# WILD64_HDI.net
KiCad netlist of a schematic drawn in EAGLE
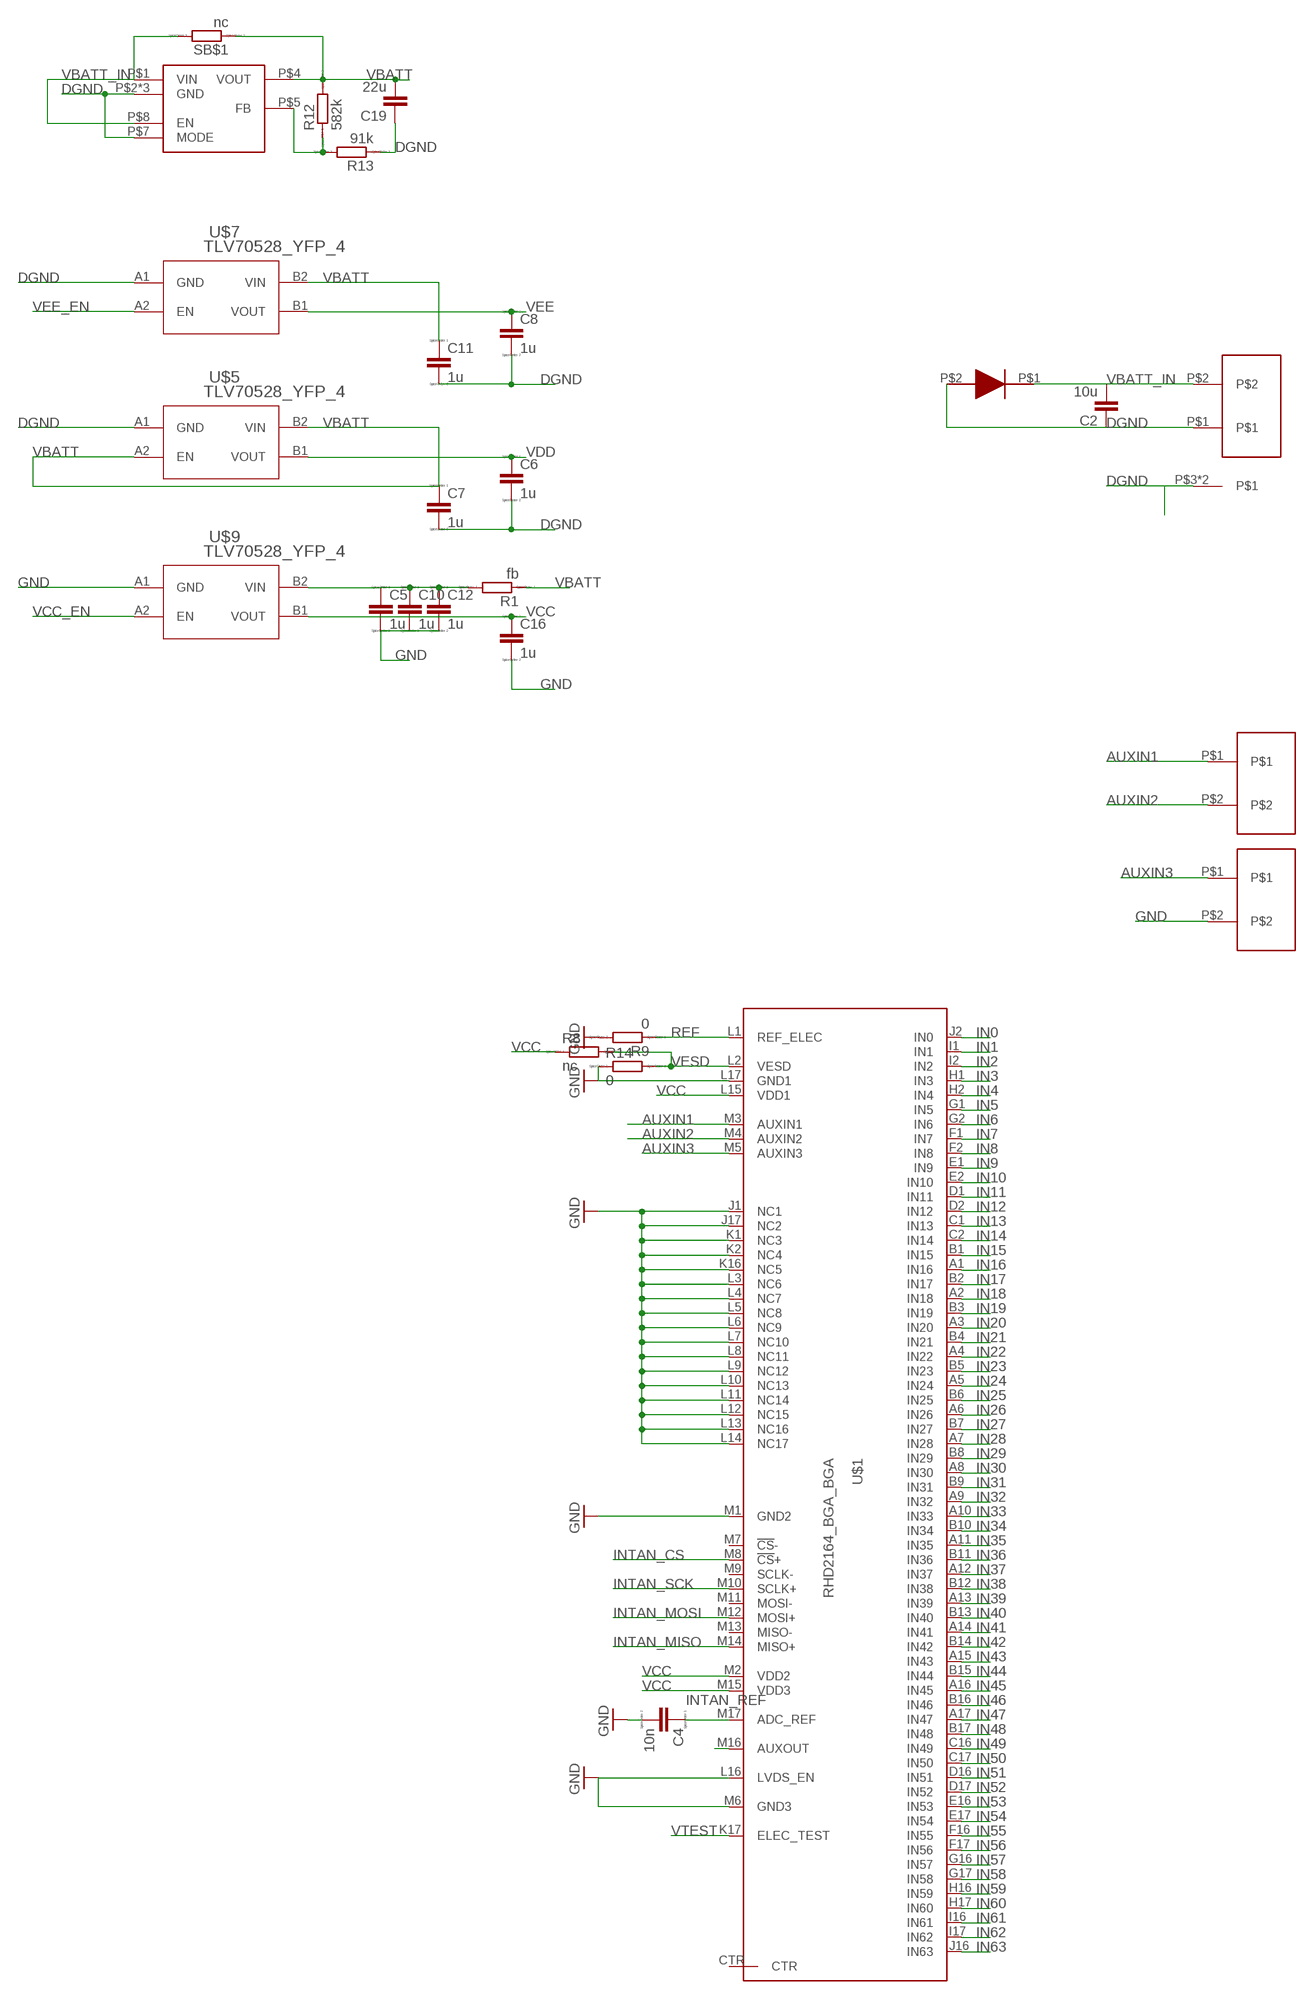
[diagram p0: schematic, sheet 1, part 1 of 2]
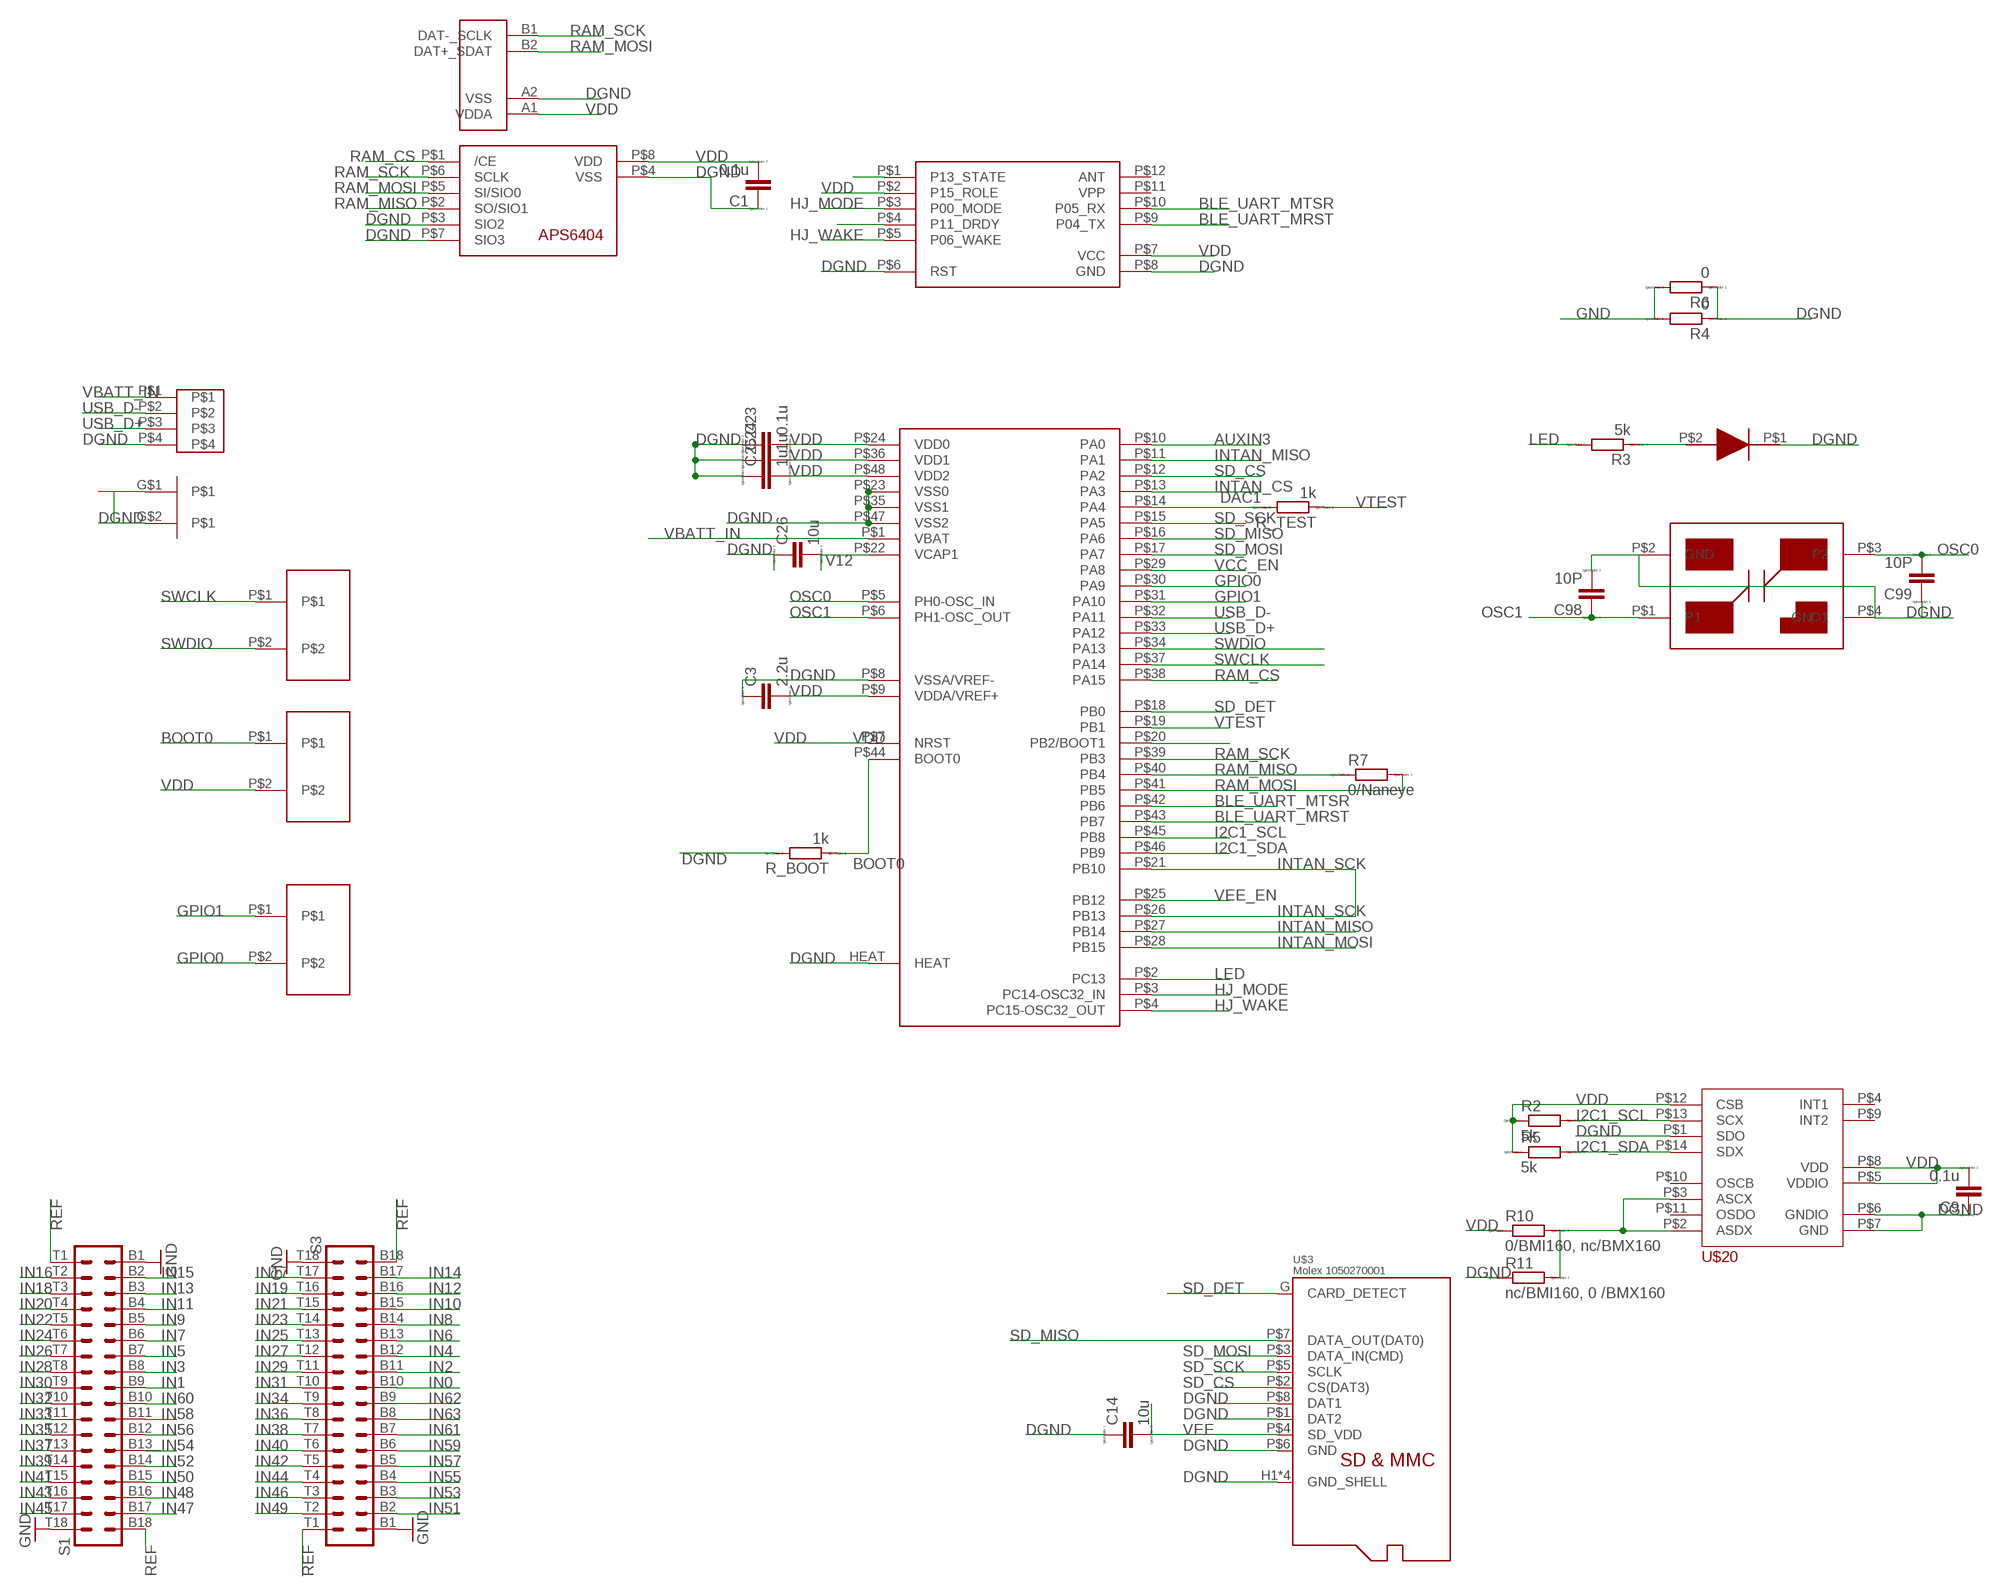
[diagram p1: schematic, sheet 1, part 2 of 2]

(export (version "E")
  (design (tool "Eeschema 10.0.6"))
  (components
    (comp (ref "C1")
      (value "0.1u")
      (footprint "eagle-import:C0201")
      (libsource (lib "eagle-import") (part "CC0201"))
    )
    (comp (ref "C2")
      (value "10u")
      (footprint "eagle-import:0402")
      (libsource (lib "eagle-import") (part "C_0402"))
    )
    (comp (ref "C3")
      (value "2.2u")
      (footprint "eagle-import:C0201")
      (libsource (lib "eagle-import") (part "CC0201"))
    )
    (comp (ref "C4")
      (value "10n")
      (footprint "eagle-import:C0201")
      (libsource (lib "eagle-import") (part "CC0201"))
    )
    (comp (ref "C5")
      (value "1u")
      (footprint "eagle-import:C0201")
      (libsource (lib "eagle-import") (part "CC0201"))
    )
    (comp (ref "C6")
      (value "1u")
      (footprint "eagle-import:C0201")
      (libsource (lib "eagle-import") (part "CC0201"))
    )
    (comp (ref "C7")
      (value "1u")
      (footprint "eagle-import:C0201")
      (libsource (lib "eagle-import") (part "CC0201"))
    )
    (comp (ref "C8")
      (value "1u")
      (footprint "eagle-import:C0201")
      (libsource (lib "eagle-import") (part "CC0201"))
    )
    (comp (ref "C9")
      (value "0.1u")
      (footprint "eagle-import:C0201")
      (libsource (lib "eagle-import") (part "CC0201"))
    )
    (comp (ref "C10")
      (value "1u")
      (footprint "eagle-import:C0201")
      (libsource (lib "eagle-import") (part "CC0201"))
    )
    (comp (ref "C11")
      (value "1u")
      (footprint "eagle-import:C0201")
      (libsource (lib "eagle-import") (part "CC0201"))
    )
    (comp (ref "C12")
      (value "1u")
      (footprint "eagle-import:C0201")
      (libsource (lib "eagle-import") (part "CC0201"))
    )
    (comp (ref "C14")
      (value "10u")
      (footprint "eagle-import:C0402")
      (libsource (lib "eagle-import") (part "CC0402"))
    )
    (comp (ref "C16")
      (value "1u")
      (footprint "eagle-import:C0201")
      (libsource (lib "eagle-import") (part "CC0201"))
    )
    (comp (ref "C19")
      (value "22u")
      (footprint "eagle-import:0402")
      (libsource (lib "eagle-import") (part "C_0402"))
    )
    (comp (ref "C23")
      (value "0.1u")
      (footprint "eagle-import:C0201")
      (libsource (lib "eagle-import") (part "CC0201"))
    )
    (comp (ref "C24")
      (value "1u")
      (footprint "eagle-import:C0201")
      (libsource (lib "eagle-import") (part "CC0201"))
    )
    (comp (ref "C25")
      (value "1u")
      (footprint "eagle-import:C0201")
      (libsource (lib "eagle-import") (part "CC0201"))
    )
    (comp (ref "C26")
      (value "10u")
      (footprint "eagle-import:C0402")
      (libsource (lib "eagle-import") (part "CC0402"))
    )
    (comp (ref "C98")
      (value "10P")
      (footprint "eagle-import:C0201")
      (libsource (lib "eagle-import") (part "CC0201"))
    )
    (comp (ref "C99")
      (value "10P")
      (footprint "eagle-import:C0201")
      (libsource (lib "eagle-import") (part "CC0201"))
    )
    (comp (ref "R1")
      (value "fb")
      (footprint "eagle-import:R0201")
      (libsource (lib "eagle-import") (part "RR0201"))
    )
    (comp (ref "R2")
      (value "5k")
      (footprint "eagle-import:R0201")
      (libsource (lib "eagle-import") (part "RR0201"))
    )
    (comp (ref "R3")
      (value "5k")
      (footprint "eagle-import:R0201")
      (libsource (lib "eagle-import") (part "RR0201"))
    )
    (comp (ref "R4")
      (value "0")
      (footprint "eagle-import:R0201")
      (libsource (lib "eagle-import") (part "RR0201"))
    )
    (comp (ref "R5")
      (value "5k")
      (footprint "eagle-import:R0201")
      (libsource (lib "eagle-import") (part "RR0201"))
    )
    (comp (ref "R6")
      (value "0")
      (footprint "eagle-import:R0201")
      (libsource (lib "eagle-import") (part "RR0201"))
    )
    (comp (ref "R7")
      (value "0/Naneye")
      (footprint "eagle-import:R0201")
      (libsource (lib "eagle-import") (part "RR0201"))
    )
    (comp (ref "R8")
      (value "nc")
      (footprint "eagle-import:R0201")
      (libsource (lib "eagle-import") (part "RR0201"))
    )
    (comp (ref "R9")
      (value "0")
      (footprint "eagle-import:R0402")
      (libsource (lib "eagle-import") (part "RR0402"))
    )
    (comp (ref "R10")
      (value "0/BMI160, nc/BMX160")
      (footprint "eagle-import:R0201")
      (libsource (lib "eagle-import") (part "RR0201"))
    )
    (comp (ref "R11")
      (value "nc/BMI160, 0 /BMX160")
      (footprint "eagle-import:R0201")
      (libsource (lib "eagle-import") (part "RR0201"))
    )
    (comp (ref "R12")
      (value "582k")
      (footprint "eagle-import:R0201")
      (libsource (lib "eagle-import") (part "RR0201"))
    )
    (comp (ref "R13")
      (value "91k")
      (footprint "eagle-import:R0201")
      (libsource (lib "eagle-import") (part "RR0201"))
    )
    (comp (ref "R14")
      (value "0")
      (footprint "eagle-import:R0201")
      (libsource (lib "eagle-import") (part "RR0201"))
    )
    (comp (ref "R_BOOT")
      (value "1k")
      (footprint "eagle-import:R0201")
      (libsource (lib "eagle-import") (part "RR0201"))
    )
    (comp (ref "R_TEST")
      (value "1k")
      (footprint "eagle-import:R0201")
      (libsource (lib "eagle-import") (part "RR0201"))
    )
    (comp (ref "S1")
      (value "OMNETICS_A79025")
      (footprint "eagle-import:OMNETICS_A79025")
      (libsource (lib "eagle-import") (part "OMNETICS_A79025"))
    )
    (comp (ref "S3")
      (value "OMNETICS_A79025")
      (footprint "eagle-import:OMNETICS_A79025")
      (libsource (lib "eagle-import") (part "OMNETICS_A79025"))
    )
    (comp (ref "SB$1")
      (value "nc")
      (footprint "eagle-import:R0201")
      (libsource (lib "eagle-import") (part "RR0201"))
    )
    (comp (ref "U$1")
      (value "RHD2164_BGA_BGA")
      (footprint "eagle-import:BGA104_9X7")
      (libsource (lib "eagle-import") (part "RHD2164_BGA_BGA"))
    )
    (comp (ref "U$2")
      (value "1.0MM_1X2VIA")
      (footprint "eagle-import:PIN_1.0MM_1X2")
      (libsource (lib "eagle-import") (part "1.0MM_1X2VIA"))
    )
    (comp (ref "U$3")
      (value "Molex 1050270001")
      (footprint "eagle-import:MICROSD_SHORT_1.7H")
      (libsource (lib "eagle-import") (part "MICROSD_SHORT_1.7H"))
    )
    (comp (ref "U$4")
      (value "NANEYECBGA")
      (footprint "eagle-import:NANEYEC_4BGA")
      (libsource (lib "eagle-import") (part "NANEYECBGA"))
    )
    (comp (ref "U$5")
      (value "TLV70528_YFP_4")
      (footprint "eagle-import:YFP4")
      (fields
        (field (name "GENERIC_PART_NUMBER") "TLV70528")
        (field (name "MANUFACTURER") "Texas Instruments")
        (field (name "MANUFACTURER_PART_NUMBER") "tlv70528_yfp_4")
      )
      (libsource (lib "eagle-import") (part "TLV70528_YFP_4"))
    )
    (comp (ref "U$6")
      (value "STM32F411_QFN48")
      (footprint "eagle-import:UFQFPN48")
      (libsource (lib "eagle-import") (part "STM32F411_QFN48"))
    )
    (comp (ref "U$7")
      (value "TLV70528_YFP_4")
      (footprint "eagle-import:YFP4")
      (fields
        (field (name "GENERIC_PART_NUMBER") "TLV70528")
        (field (name "MANUFACTURER") "Texas Instruments")
        (field (name "MANUFACTURER_PART_NUMBER") "tlv70528_yfp_4")
      )
      (libsource (lib "eagle-import") (part "TLV70528_YFP_4"))
    )
    (comp (ref "U$8")
      (value "1.27MM_1X2CONN")
      (footprint "eagle-import:1.27MM_1X2")
      (libsource (lib "eagle-import") (part "1.27MM_1X2CONN"))
    )
    (comp (ref "U$9")
      (value "TLV70528_YFP_4")
      (footprint "eagle-import:YFP4")
      (fields
        (field (name "GENERIC_PART_NUMBER") "TLV70528")
        (field (name "MANUFACTURER") "Texas Instruments")
        (field (name "MANUFACTURER_PART_NUMBER") "tlv70528_yfp_4")
      )
      (libsource (lib "eagle-import") (part "TLV70528_YFP_4"))
    )
    (comp (ref "U$10")
      (value "HJ580")
      (footprint "eagle-import:HJ580")
      (libsource (lib "eagle-import") (part "HJ580"))
    )
    (comp (ref "U$11")
      (value "DIODE0402")
      (footprint "eagle-import:0402_LED")
      (libsource (lib "eagle-import") (part "DIODE0402"))
    )
    (comp (ref "U$12")
      (value "1.0MM_1X4PAD")
      (footprint "eagle-import:1.0MM_CONN_1X4_SMD")
      (libsource (lib "eagle-import") (part "1.0MM_1X4PAD"))
    )
    (comp (ref "U$13")
      (value "1.00MM_1X2PAD")
      (footprint "eagle-import:1.0MM_CONN_1X2_SMD")
      (libsource (lib "eagle-import") (part "1.00MM_1X2PAD"))
    )
    (comp (ref "U$14")
      (value "APS6404")
      (footprint "eagle-import:USON-8L_3X2")
      (libsource (lib "eagle-import") (part "APS6404"))
    )
    (comp (ref "U$15")
      (value "ABM12_CRYSTAL")
      (footprint "eagle-import:SMD4_1.6MMX1.2MM")
      (libsource (lib "eagle-import") (part "ABM12_CRYSTAL"))
    )
    (comp (ref "U$16")
      (value "DIODE0402")
      (footprint "eagle-import:0402_LED")
      (libsource (lib "eagle-import") (part "DIODE0402"))
    )
    (comp (ref "U$17")
      (value "1.27MM_1X2CONN")
      (footprint "eagle-import:1.27MM_1X2")
      (libsource (lib "eagle-import") (part "1.27MM_1X2CONN"))
    )
    (comp (ref "U$18")
      (value "1.27MM_1X2CONN")
      (footprint "eagle-import:1.27MM_1X2")
      (libsource (lib "eagle-import") (part "1.27MM_1X2CONN"))
    )
    (comp (ref "U$19")
      (value "1.27MM_1X2CONN")
      (footprint "eagle-import:1.27MM_1X2")
      (libsource (lib "eagle-import") (part "1.27MM_1X2CONN"))
    )
    (comp (ref "U$20")
      (value "BMI27014")
      (footprint "eagle-import:14_VFLGA")
      (libsource (lib "eagle-import") (part "BMI27014"))
    )
    (comp (ref "U$22")
      (value "TPSM83100")
      (footprint "eagle-import:MICROSIP_SIU0008A")
      (libsource (lib "eagle-import") (part "TPSM83100"))
    )
  )
  (nets
    (net (code "1") (name "/AUXIN1") (class "Default")
      (node (ref "U$1") (pin "M3") (pinfunction "AUXIN1_M3") (pintype "input"))
      (node (ref "U$19") (pin "P$1") (pinfunction "P$1_P$1") (pintype "bidirectional"))
    )
    (net (code "2") (name "/AUXIN2") (class "Default")
      (node (ref "U$1") (pin "M4") (pinfunction "AUXIN2_M4") (pintype "input"))
      (node (ref "U$19") (pin "P$2") (pinfunction "P$2_P$2") (pintype "bidirectional"))
    )
    (net (code "3") (name "/AUXIN3") (class "Default")
      (node (ref "U$1") (pin "M5") (pinfunction "AUXIN3_M5") (pintype "input"))
      (node (ref "U$18") (pin "P$1") (pinfunction "P$1_P$1") (pintype "bidirectional"))
      (node (ref "U$6") (pin "P$10") (pinfunction "PA0_P$10") (pintype "bidirectional"))
    )
    (net (code "4") (name "/BLE_UART_MRST") (class "Default")
      (node (ref "U$10") (pin "P$9") (pinfunction "P04_TX_P$9") (pintype "bidirectional"))
      (node (ref "U$6") (pin "P$43") (pinfunction "PB7_P$43") (pintype "bidirectional"))
    )
    (net (code "5") (name "/BLE_UART_MTSR") (class "Default")
      (node (ref "U$10") (pin "P$10") (pinfunction "P05_RX_P$10") (pintype "bidirectional"))
      (node (ref "U$6") (pin "P$42") (pinfunction "PB6_P$42") (pintype "bidirectional"))
    )
    (net (code "6") (name "/BOOT0") (class "Default")
      (node (ref "R_BOOT") (pin "1") (pinfunction "1_1") (pintype "passive"))
      (node (ref "U$6") (pin "P$44") (pinfunction "BOOT0_P$44") (pintype "bidirectional"))
      (node (ref "U$8") (pin "P$1") (pinfunction "P$1_P$1") (pintype "bidirectional"))
    )
    (net (code "7") (name "/DAC1") (class "Default")
      (node (ref "R_TEST") (pin "2") (pinfunction "2_2") (pintype "passive"))
      (node (ref "U$6") (pin "P$14") (pinfunction "PA4_P$14") (pintype "bidirectional"))
    )
    (net (code "8") (name "/DGND") (class "Default")
      (node (ref "C1") (pin "1") (pinfunction "1_1") (pintype "passive"))
      (node (ref "C11") (pin "2") (pinfunction "2_2") (pintype "passive"))
      (node (ref "C14") (pin "1") (pinfunction "1_1") (pintype "passive"))
      (node (ref "C19") (pin "1") (pinfunction "1_1") (pintype "passive"))
      (node (ref "C2") (pin "1") (pinfunction "1_1") (pintype "passive"))
      (node (ref "C23") (pin "1") (pinfunction "1_1") (pintype "passive"))
      (node (ref "C24") (pin "1") (pinfunction "1_1") (pintype "passive"))
      (node (ref "C25") (pin "1") (pinfunction "1_1") (pintype "passive"))
      (node (ref "C26") (pin "1") (pinfunction "1_1") (pintype "passive"))
      (node (ref "C3") (pin "1") (pinfunction "1_1") (pintype "passive"))
      (node (ref "C6") (pin "2") (pinfunction "2_2") (pintype "passive"))
      (node (ref "C7") (pin "2") (pinfunction "2_2") (pintype "passive"))
      (node (ref "C8") (pin "2") (pinfunction "2_2") (pintype "passive"))
      (node (ref "C9") (pin "1") (pinfunction "1_1") (pintype "passive"))
      (node (ref "C98") (pin "2") (pinfunction "2_2") (pintype "passive"))
      (node (ref "C99") (pin "1") (pinfunction "1_1") (pintype "passive"))
      (node (ref "R11") (pin "1") (pinfunction "1_1") (pintype "passive"))
      (node (ref "R13") (pin "1") (pinfunction "1_1") (pintype "passive"))
      (node (ref "R4") (pin "1") (pinfunction "1_1") (pintype "passive"))
      (node (ref "R6") (pin "1") (pinfunction "1_1") (pintype "passive"))
      (node (ref "R_BOOT") (pin "2") (pinfunction "2_2") (pintype "passive"))
      (node (ref "U$10") (pin "P$6") (pinfunction "RST_P$6") (pintype "bidirectional"))
      (node (ref "U$10") (pin "P$8") (pinfunction "GND_P$8") (pintype "bidirectional"))
      (node (ref "U$11") (pin "P$2") (pinfunction "IN_P$2") (pintype "passive"))
      (node (ref "U$12") (pin "G$1") (pinfunction "P$1_G$1") (pintype "bidirectional"))
      (node (ref "U$12") (pin "G$2") (pinfunction "P$1_G$2") (pintype "bidirectional"))
      (node (ref "U$12") (pin "P$4") (pinfunction "P$4_P$4") (pintype "bidirectional"))
      (node (ref "U$13") (pin "P$1") (pinfunction "P$1_P$1") (pintype "bidirectional"))
      (node (ref "U$13") (pin "P$3") (pinfunction "P$1_P$3") (pintype "bidirectional"))
      (node (ref "U$13") (pin "P$4") (pinfunction "P$1_P$4") (pintype "bidirectional"))
      (node (ref "U$14") (pin "P$3") (pinfunction "SIO2_P$3") (pintype "bidirectional"))
      (node (ref "U$14") (pin "P$4") (pinfunction "VSS_P$4") (pintype "bidirectional"))
      (node (ref "U$14") (pin "P$7") (pinfunction "SIO3_P$7") (pintype "bidirectional"))
      (node (ref "U$15") (pin "P$2") (pinfunction "GND_P$2") (pintype "bidirectional"))
      (node (ref "U$15") (pin "P$4") (pinfunction "GND1_P$4") (pintype "bidirectional"))
      (node (ref "U$16") (pin "P$1") (pinfunction "OUT_P$1") (pintype "passive"))
      (node (ref "U$20") (pin "P$1") (pinfunction "SDO_P$1") (pintype "bidirectional"))
      (node (ref "U$20") (pin "P$6") (pinfunction "GNDIO_P$6") (pintype "bidirectional"))
      (node (ref "U$20") (pin "P$7") (pinfunction "GND_P$7") (pintype "bidirectional"))
      (node (ref "U$22") (pin "P$2") (pinfunction "GND_P$2") (pintype "bidirectional"))
      (node (ref "U$22") (pin "P$3") (pinfunction "GND_P$3") (pintype "bidirectional"))
      (node (ref "U$22") (pin "P$6") (pinfunction "GND_P$6") (pintype "bidirectional"))
      (node (ref "U$22") (pin "P$7") (pinfunction "MODE_P$7") (pintype "bidirectional"))
      (node (ref "U$3") (pin "H1") (pinfunction "GND_SHELL_H1") (pintype "power_in"))
      (node (ref "U$3") (pin "H2") (pinfunction "GND_SHELL_H2") (pintype "power_in"))
      (node (ref "U$3") (pin "H3") (pinfunction "GND_SHELL_H3") (pintype "power_in"))
      (node (ref "U$3") (pin "H4") (pinfunction "GND_SHELL_H4") (pintype "power_in"))
      (node (ref "U$3") (pin "P$1") (pinfunction "DAT2_P$1") (pintype "bidirectional"))
      (node (ref "U$3") (pin "P$6") (pinfunction "GND_P$6") (pintype "power_in"))
      (node (ref "U$3") (pin "P$8") (pinfunction "DAT1_P$8") (pintype "bidirectional"))
      (node (ref "U$4") (pin "A2") (pinfunction "VSS_A2") (pintype "bidirectional"))
      (node (ref "U$5") (pin "A1") (pinfunction "GND_A1") (pintype "power_in"))
      (node (ref "U$6") (pin "HEAT") (pinfunction "HEAT_HEAT") (pintype "bidirectional"))
      (node (ref "U$6") (pin "P$23") (pinfunction "VSS0_P$23") (pintype "bidirectional"))
      (node (ref "U$6") (pin "P$35") (pinfunction "VSS1_P$35") (pintype "bidirectional"))
      (node (ref "U$6") (pin "P$47") (pinfunction "VSS2_P$47") (pintype "bidirectional"))
      (node (ref "U$6") (pin "P$8") (pinfunction "VSSA/VREF-_P$8") (pintype "bidirectional"))
      (node (ref "U$7") (pin "A1") (pinfunction "GND_A1") (pintype "power_in"))
    )
    (net (code "9") (name "/GPIO0") (class "Default")
      (node (ref "U$17") (pin "P$2") (pinfunction "P$2_P$2") (pintype "bidirectional"))
      (node (ref "U$6") (pin "P$30") (pinfunction "PA9_P$30") (pintype "bidirectional"))
    )
    (net (code "10") (name "/GPIO1") (class "Default")
      (node (ref "U$17") (pin "P$1") (pinfunction "P$1_P$1") (pintype "bidirectional"))
      (node (ref "U$6") (pin "P$31") (pinfunction "PA10_P$31") (pintype "bidirectional"))
    )
    (net (code "11") (name "/HJ_MODE") (class "Default")
      (node (ref "U$10") (pin "P$3") (pinfunction "P00_MODE_P$3") (pintype "bidirectional"))
      (node (ref "U$6") (pin "P$3") (pinfunction "PC14-OSC32_IN_P$3") (pintype "bidirectional"))
    )
    (net (code "12") (name "/HJ_WAKE") (class "Default")
      (node (ref "U$10") (pin "P$5") (pinfunction "P06_WAKE_P$5") (pintype "bidirectional"))
      (node (ref "U$6") (pin "P$4") (pinfunction "PC15-OSC32_OUT_P$4") (pintype "bidirectional"))
    )
    (net (code "13") (name "/I2C1_SCL") (class "Default")
      (node (ref "R2") (pin "2") (pinfunction "2_2") (pintype "passive"))
      (node (ref "U$20") (pin "P$13") (pinfunction "SCX_P$13") (pintype "bidirectional"))
      (node (ref "U$6") (pin "P$45") (pinfunction "PB8_P$45") (pintype "bidirectional"))
    )
    (net (code "14") (name "/I2C1_SDA") (class "Default")
      (node (ref "R5") (pin "2") (pinfunction "2_2") (pintype "passive"))
      (node (ref "U$20") (pin "P$14") (pinfunction "SDX_P$14") (pintype "bidirectional"))
      (node (ref "U$6") (pin "P$46") (pinfunction "PB9_P$46") (pintype "bidirectional"))
    )
    (net (code "15") (name "/IN0") (class "Default")
      (node (ref "S3") (pin "B10") (pinfunction "B10_B10") (pintype "passive"))
      (node (ref "U$1") (pin "J2") (pinfunction "IN0_J2") (pintype "input"))
    )
    (net (code "16") (name "/IN1") (class "Default")
      (node (ref "S1") (pin "B9") (pinfunction "B9_B9") (pintype "passive"))
      (node (ref "U$1") (pin "I1") (pinfunction "IN1_I1") (pintype "input"))
    )
    (net (code "17") (name "/IN2") (class "Default")
      (node (ref "S3") (pin "B11") (pinfunction "B11_B11") (pintype "passive"))
      (node (ref "U$1") (pin "I2") (pinfunction "IN2_I2") (pintype "input"))
    )
    (net (code "18") (name "/IN3") (class "Default")
      (node (ref "S1") (pin "B8") (pinfunction "B8_B8") (pintype "passive"))
      (node (ref "U$1") (pin "H1") (pinfunction "IN3_H1") (pintype "input"))
    )
    (net (code "19") (name "/IN4") (class "Default")
      (node (ref "S3") (pin "B12") (pinfunction "B12_B12") (pintype "passive"))
      (node (ref "U$1") (pin "H2") (pinfunction "IN4_H2") (pintype "input"))
    )
    (net (code "20") (name "/IN5") (class "Default")
      (node (ref "S1") (pin "B7") (pinfunction "B7_B7") (pintype "passive"))
      (node (ref "U$1") (pin "G1") (pinfunction "IN5_G1") (pintype "input"))
    )
    (net (code "21") (name "/IN6") (class "Default")
      (node (ref "S3") (pin "B13") (pinfunction "B13_B13") (pintype "passive"))
      (node (ref "U$1") (pin "G2") (pinfunction "IN6_G2") (pintype "input"))
    )
    (net (code "22") (name "/IN7") (class "Default")
      (node (ref "S1") (pin "B6") (pinfunction "B6_B6") (pintype "passive"))
      (node (ref "U$1") (pin "F1") (pinfunction "IN7_F1") (pintype "input"))
    )
    (net (code "23") (name "/IN8") (class "Default")
      (node (ref "S3") (pin "B14") (pinfunction "B14_B14") (pintype "passive"))
      (node (ref "U$1") (pin "F2") (pinfunction "IN8_F2") (pintype "input"))
    )
    (net (code "24") (name "/IN9") (class "Default")
      (node (ref "S1") (pin "B5") (pinfunction "B5_B5") (pintype "passive"))
      (node (ref "U$1") (pin "E1") (pinfunction "IN9_E1") (pintype "input"))
    )
    (net (code "25") (name "/IN10") (class "Default")
      (node (ref "S3") (pin "B15") (pinfunction "B15_B15") (pintype "passive"))
      (node (ref "U$1") (pin "E2") (pinfunction "IN10_E2") (pintype "input"))
    )
    (net (code "26") (name "/IN11") (class "Default")
      (node (ref "S1") (pin "B4") (pinfunction "B4_B4") (pintype "passive"))
      (node (ref "U$1") (pin "D1") (pinfunction "IN11_D1") (pintype "input"))
    )
    (net (code "27") (name "/IN12") (class "Default")
      (node (ref "S3") (pin "B16") (pinfunction "B16_B16") (pintype "passive"))
      (node (ref "U$1") (pin "D2") (pinfunction "IN12_D2") (pintype "input"))
    )
    (net (code "28") (name "/IN13") (class "Default")
      (node (ref "S1") (pin "B3") (pinfunction "B3_B3") (pintype "passive"))
      (node (ref "U$1") (pin "C1") (pinfunction "IN13_C1") (pintype "input"))
    )
    (net (code "29") (name "/IN14") (class "Default")
      (node (ref "S3") (pin "B17") (pinfunction "B17_B17") (pintype "passive"))
      (node (ref "U$1") (pin "C2") (pinfunction "IN14_C2") (pintype "input"))
    )
    (net (code "30") (name "/IN15") (class "Default")
      (node (ref "S1") (pin "B2") (pinfunction "B2_B2") (pintype "passive"))
      (node (ref "U$1") (pin "B1") (pinfunction "IN15_B1") (pintype "input"))
    )
    (net (code "31") (name "/IN16") (class "Default")
      (node (ref "S1") (pin "T2") (pinfunction "T2_T2") (pintype "passive"))
      (node (ref "U$1") (pin "A1") (pinfunction "IN16_A1") (pintype "input"))
    )
    (net (code "32") (name "/IN17") (class "Default")
      (node (ref "S3") (pin "T17") (pinfunction "T17_T17") (pintype "passive"))
      (node (ref "U$1") (pin "B2") (pinfunction "IN17_B2") (pintype "input"))
    )
    (net (code "33") (name "/IN18") (class "Default")
      (node (ref "S1") (pin "T3") (pinfunction "T3_T3") (pintype "passive"))
      (node (ref "U$1") (pin "A2") (pinfunction "IN18_A2") (pintype "input"))
    )
    (net (code "34") (name "/IN19") (class "Default")
      (node (ref "S3") (pin "T16") (pinfunction "T16_T16") (pintype "passive"))
      (node (ref "U$1") (pin "B3") (pinfunction "IN19_B3") (pintype "input"))
    )
    (net (code "35") (name "/IN20") (class "Default")
      (node (ref "S1") (pin "T4") (pinfunction "T4_T4") (pintype "passive"))
      (node (ref "U$1") (pin "A3") (pinfunction "IN20_A3") (pintype "input"))
    )
    (net (code "36") (name "/IN21") (class "Default")
      (node (ref "S3") (pin "T15") (pinfunction "T15_T15") (pintype "passive"))
      (node (ref "U$1") (pin "B4") (pinfunction "IN21_B4") (pintype "input"))
    )
    (net (code "37") (name "/IN22") (class "Default")
      (node (ref "S1") (pin "T5") (pinfunction "T5_T5") (pintype "passive"))
      (node (ref "U$1") (pin "A4") (pinfunction "IN22_A4") (pintype "input"))
    )
    (net (code "38") (name "/IN23") (class "Default")
      (node (ref "S3") (pin "T14") (pinfunction "T14_T14") (pintype "passive"))
      (node (ref "U$1") (pin "B5") (pinfunction "IN23_B5") (pintype "input"))
    )
    (net (code "39") (name "/IN24") (class "Default")
      (node (ref "S1") (pin "T6") (pinfunction "T6_T6") (pintype "passive"))
      (node (ref "U$1") (pin "A5") (pinfunction "IN24_A5") (pintype "input"))
    )
    (net (code "40") (name "/IN25") (class "Default")
      (node (ref "S3") (pin "T13") (pinfunction "T13_T13") (pintype "passive"))
      (node (ref "U$1") (pin "B6") (pinfunction "IN25_B6") (pintype "input"))
    )
    (net (code "41") (name "/IN26") (class "Default")
      (node (ref "S1") (pin "T7") (pinfunction "T7_T7") (pintype "passive"))
      (node (ref "U$1") (pin "A6") (pinfunction "IN26_A6") (pintype "input"))
    )
    (net (code "42") (name "/IN27") (class "Default")
      (node (ref "S3") (pin "T12") (pinfunction "T12_T12") (pintype "passive"))
      (node (ref "U$1") (pin "B7") (pinfunction "IN27_B7") (pintype "input"))
    )
    (net (code "43") (name "/IN28") (class "Default")
      (node (ref "S1") (pin "T8") (pinfunction "T8_T8") (pintype "passive"))
      (node (ref "U$1") (pin "A7") (pinfunction "IN28_A7") (pintype "input"))
    )
    (net (code "44") (name "/IN29") (class "Default")
      (node (ref "S3") (pin "T11") (pinfunction "T11_T11") (pintype "passive"))
      (node (ref "U$1") (pin "B8") (pinfunction "IN29_B8") (pintype "input"))
    )
    (net (code "45") (name "/IN30") (class "Default")
      (node (ref "S1") (pin "T9") (pinfunction "T9_T9") (pintype "passive"))
      (node (ref "U$1") (pin "A8") (pinfunction "IN30_A8") (pintype "input"))
    )
    (net (code "46") (name "/IN31") (class "Default")
      (node (ref "S3") (pin "T10") (pinfunction "T10_T10") (pintype "passive"))
      (node (ref "U$1") (pin "B9") (pinfunction "IN31_B9") (pintype "input"))
    )
    (net (code "47") (name "/IN32") (class "Default")
      (node (ref "S1") (pin "T10") (pinfunction "T10_T10") (pintype "passive"))
      (node (ref "U$1") (pin "A9") (pinfunction "IN32_A9") (pintype "input"))
    )
    (net (code "48") (name "/IN33") (class "Default")
      (node (ref "S1") (pin "T11") (pinfunction "T11_T11") (pintype "passive"))
      (node (ref "U$1") (pin "A10") (pinfunction "IN33_A10") (pintype "input"))
    )
    (net (code "49") (name "/IN34") (class "Default")
      (node (ref "S3") (pin "T9") (pinfunction "T9_T9") (pintype "passive"))
      (node (ref "U$1") (pin "B10") (pinfunction "IN34_B10") (pintype "input"))
    )
    (net (code "50") (name "/IN35") (class "Default")
      (node (ref "S1") (pin "T12") (pinfunction "T12_T12") (pintype "passive"))
      (node (ref "U$1") (pin "A11") (pinfunction "IN35_A11") (pintype "input"))
    )
    (net (code "51") (name "/IN36") (class "Default")
      (node (ref "S3") (pin "T8") (pinfunction "T8_T8") (pintype "passive"))
      (node (ref "U$1") (pin "B11") (pinfunction "IN36_B11") (pintype "input"))
    )
    (net (code "52") (name "/IN37") (class "Default")
      (node (ref "S1") (pin "T13") (pinfunction "T13_T13") (pintype "passive"))
      (node (ref "U$1") (pin "A12") (pinfunction "IN37_A12") (pintype "input"))
    )
    (net (code "53") (name "/IN38") (class "Default")
      (node (ref "S3") (pin "T7") (pinfunction "T7_T7") (pintype "passive"))
      (node (ref "U$1") (pin "B12") (pinfunction "IN38_B12") (pintype "input"))
    )
    (net (code "54") (name "/IN39") (class "Default")
      (node (ref "S1") (pin "T14") (pinfunction "T14_T14") (pintype "passive"))
      (node (ref "U$1") (pin "A13") (pinfunction "IN39_A13") (pintype "input"))
    )
    (net (code "55") (name "/IN40") (class "Default")
      (node (ref "S3") (pin "T6") (pinfunction "T6_T6") (pintype "passive"))
      (node (ref "U$1") (pin "B13") (pinfunction "IN40_B13") (pintype "input"))
    )
    (net (code "56") (name "/IN41") (class "Default")
      (node (ref "S1") (pin "T15") (pinfunction "T15_T15") (pintype "passive"))
      (node (ref "U$1") (pin "A14") (pinfunction "IN41_A14") (pintype "input"))
    )
    (net (code "57") (name "/IN42") (class "Default")
      (node (ref "S3") (pin "T5") (pinfunction "T5_T5") (pintype "passive"))
      (node (ref "U$1") (pin "B14") (pinfunction "IN42_B14") (pintype "input"))
    )
    (net (code "58") (name "/IN43") (class "Default")
      (node (ref "S1") (pin "T16") (pinfunction "T16_T16") (pintype "passive"))
      (node (ref "U$1") (pin "A15") (pinfunction "IN43_A15") (pintype "input"))
    )
    (net (code "59") (name "/IN44") (class "Default")
      (node (ref "S3") (pin "T4") (pinfunction "T4_T4") (pintype "passive"))
      (node (ref "U$1") (pin "B15") (pinfunction "IN44_B15") (pintype "input"))
    )
    (net (code "60") (name "/IN45") (class "Default")
      (node (ref "S1") (pin "T17") (pinfunction "T17_T17") (pintype "passive"))
      (node (ref "U$1") (pin "A16") (pinfunction "IN45_A16") (pintype "input"))
    )
    (net (code "61") (name "/IN46") (class "Default")
      (node (ref "S3") (pin "T3") (pinfunction "T3_T3") (pintype "passive"))
      (node (ref "U$1") (pin "B16") (pinfunction "IN46_B16") (pintype "input"))
    )
    (net (code "62") (name "/IN47") (class "Default")
      (node (ref "S1") (pin "B17") (pinfunction "B17_B17") (pintype "passive"))
      (node (ref "U$1") (pin "A17") (pinfunction "IN47_A17") (pintype "input"))
    )
    (net (code "63") (name "/IN48") (class "Default")
      (node (ref "S1") (pin "B16") (pinfunction "B16_B16") (pintype "passive"))
      (node (ref "U$1") (pin "B17") (pinfunction "IN48_B17") (pintype "input"))
    )
    (net (code "64") (name "/IN49") (class "Default")
      (node (ref "S3") (pin "T2") (pinfunction "T2_T2") (pintype "passive"))
      (node (ref "U$1") (pin "C16") (pinfunction "IN49_C16") (pintype "input"))
    )
    (net (code "65") (name "/IN50") (class "Default")
      (node (ref "S1") (pin "B15") (pinfunction "B15_B15") (pintype "passive"))
      (node (ref "U$1") (pin "C17") (pinfunction "IN50_C17") (pintype "input"))
    )
    (net (code "66") (name "/IN51") (class "Default")
      (node (ref "S3") (pin "B2") (pinfunction "B2_B2") (pintype "passive"))
      (node (ref "U$1") (pin "D16") (pinfunction "IN51_D16") (pintype "input"))
    )
    (net (code "67") (name "/IN52") (class "Default")
      (node (ref "S1") (pin "B14") (pinfunction "B14_B14") (pintype "passive"))
      (node (ref "U$1") (pin "D17") (pinfunction "IN52_D17") (pintype "input"))
    )
    (net (code "68") (name "/IN53") (class "Default")
      (node (ref "S3") (pin "B3") (pinfunction "B3_B3") (pintype "passive"))
      (node (ref "U$1") (pin "E16") (pinfunction "IN53_E16") (pintype "input"))
    )
    (net (code "69") (name "/IN54") (class "Default")
      (node (ref "S1") (pin "B13") (pinfunction "B13_B13") (pintype "passive"))
      (node (ref "U$1") (pin "E17") (pinfunction "IN54_E17") (pintype "input"))
    )
    (net (code "70") (name "/IN55") (class "Default")
      (node (ref "S3") (pin "B4") (pinfunction "B4_B4") (pintype "passive"))
      (node (ref "U$1") (pin "F16") (pinfunction "IN55_F16") (pintype "input"))
    )
    (net (code "71") (name "/IN56") (class "Default")
      (node (ref "S1") (pin "B12") (pinfunction "B12_B12") (pintype "passive"))
      (node (ref "U$1") (pin "F17") (pinfunction "IN56_F17") (pintype "input"))
    )
    (net (code "72") (name "/IN57") (class "Default")
      (node (ref "S3") (pin "B5") (pinfunction "B5_B5") (pintype "passive"))
      (node (ref "U$1") (pin "G16") (pinfunction "IN57_G16") (pintype "input"))
    )
    (net (code "73") (name "/IN58") (class "Default")
      (node (ref "S1") (pin "B11") (pinfunction "B11_B11") (pintype "passive"))
      (node (ref "U$1") (pin "G17") (pinfunction "IN58_G17") (pintype "input"))
    )
    (net (code "74") (name "/IN59") (class "Default")
      (node (ref "S3") (pin "B6") (pinfunction "B6_B6") (pintype "passive"))
      (node (ref "U$1") (pin "H16") (pinfunction "IN59_H16") (pintype "input"))
    )
    (net (code "75") (name "/IN60") (class "Default")
      (node (ref "S1") (pin "B10") (pinfunction "B10_B10") (pintype "passive"))
      (node (ref "U$1") (pin "H17") (pinfunction "IN60_H17") (pintype "input"))
    )
    (net (code "76") (name "/IN61") (class "Default")
      (node (ref "S3") (pin "B7") (pinfunction "B7_B7") (pintype "passive"))
      (node (ref "U$1") (pin "I16") (pinfunction "IN61_I16") (pintype "input"))
    )
    (net (code "77") (name "/IN62") (class "Default")
      (node (ref "S3") (pin "B9") (pinfunction "B9_B9") (pintype "passive"))
      (node (ref "U$1") (pin "I17") (pinfunction "IN62_I17") (pintype "input"))
    )
    (net (code "78") (name "/IN63") (class "Default")
      (node (ref "S3") (pin "B8") (pinfunction "B8_B8") (pintype "passive"))
      (node (ref "U$1") (pin "J16") (pinfunction "IN63_J16") (pintype "input"))
    )
    (net (code "79") (name "/INTAN_CS") (class "Default")
      (node (ref "U$1") (pin "M8") (pinfunction "~{CS}+_M8") (pintype "input"))
      (node (ref "U$6") (pin "P$13") (pinfunction "PA3_P$13") (pintype "bidirectional"))
    )
    (net (code "80") (name "/INTAN_MISO") (class "Default")
      (node (ref "U$1") (pin "M14") (pinfunction "MISO+_M14") (pintype "output"))
      (node (ref "U$6") (pin "P$11") (pinfunction "PA1_P$11") (pintype "bidirectional"))
      (node (ref "U$6") (pin "P$27") (pinfunction "PB14_P$27") (pintype "bidirectional"))
    )
    (net (code "81") (name "/INTAN_MOSI") (class "Default")
      (node (ref "U$1") (pin "M12") (pinfunction "MOSI+_M12") (pintype "input"))
      (node (ref "U$6") (pin "P$28") (pinfunction "PB15_P$28") (pintype "bidirectional"))
    )
    (net (code "82") (name "/INTAN_REF") (class "Default")
      (node (ref "C4") (pin "1") (pinfunction "1_1") (pintype "passive"))
      (node (ref "U$1") (pin "M17") (pinfunction "ADC_REF_M17") (pintype "passive"))
    )
    (net (code "83") (name "/INTAN_SCK") (class "Default")
      (node (ref "U$1") (pin "M10") (pinfunction "SCLK+_M10") (pintype "input"))
      (node (ref "U$6") (pin "P$21") (pinfunction "PB10_P$21") (pintype "bidirectional"))
      (node (ref "U$6") (pin "P$26") (pinfunction "PB13_P$26") (pintype "bidirectional"))
    )
    (net (code "84") (name "/LED") (class "Default")
      (node (ref "R3") (pin "2") (pinfunction "2_2") (pintype "passive"))
      (node (ref "U$6") (pin "P$2") (pinfunction "PC13_P$2") (pintype "bidirectional"))
    )
    (net (code "85") (name "/OSC0") (class "Default")
      (node (ref "C99") (pin "2") (pinfunction "2_2") (pintype "passive"))
      (node (ref "U$15") (pin "P$3") (pinfunction "P2_P$3") (pintype "bidirectional"))
      (node (ref "U$6") (pin "P$5") (pinfunction "PH0-OSC_IN_P$5") (pintype "bidirectional"))
    )
    (net (code "86") (name "/OSC1") (class "Default")
      (node (ref "C98") (pin "1") (pinfunction "1_1") (pintype "passive"))
      (node (ref "U$15") (pin "P$1") (pinfunction "P1_P$1") (pintype "bidirectional"))
      (node (ref "U$6") (pin "P$6") (pinfunction "PH1-OSC_OUT_P$6") (pintype "bidirectional"))
    )
    (net (code "87") (name "/RAM_CS") (class "Default")
      (node (ref "U$14") (pin "P$1") (pinfunction "/CE_P$1") (pintype "bidirectional"))
      (node (ref "U$6") (pin "P$38") (pinfunction "PA15_P$38") (pintype "bidirectional"))
    )
    (net (code "88") (name "/RAM_MISO") (class "Default")
      (node (ref "R7") (pin "1") (pinfunction "1_1") (pintype "passive"))
      (node (ref "U$14") (pin "P$2") (pinfunction "SO/SIO1_P$2") (pintype "bidirectional"))
      (node (ref "U$6") (pin "P$40") (pinfunction "PB4_P$40") (pintype "bidirectional"))
    )
    (net (code "89") (name "/RAM_MOSI") (class "Default")
      (node (ref "R7") (pin "2") (pinfunction "2_2") (pintype "passive"))
      (node (ref "U$14") (pin "P$5") (pinfunction "SI/SIO0_P$5") (pintype "bidirectional"))
      (node (ref "U$4") (pin "B2") (pinfunction "DAT+_SDAT_B2") (pintype "bidirectional"))
      (node (ref "U$6") (pin "P$41") (pinfunction "PB5_P$41") (pintype "bidirectional"))
    )
    (net (code "90") (name "/RAM_SCK") (class "Default")
      (node (ref "U$14") (pin "P$6") (pinfunction "SCLK_P$6") (pintype "bidirectional"))
      (node (ref "U$4") (pin "B1") (pinfunction "DAT-_SCLK_B1") (pintype "bidirectional"))
      (node (ref "U$6") (pin "P$39") (pinfunction "PB3_P$39") (pintype "bidirectional"))
    )
    (net (code "91") (name "/REF") (class "Default")
      (node (ref "R9") (pin "1") (pinfunction "1_1") (pintype "passive"))
      (node (ref "S1") (pin "B18") (pinfunction "B18_B18") (pintype "passive"))
      (node (ref "S1") (pin "T1") (pinfunction "T1_T1") (pintype "passive"))
      (node (ref "S3") (pin "B18") (pinfunction "B18_B18") (pintype "passive"))
      (node (ref "S3") (pin "T1") (pinfunction "T1_T1") (pintype "passive"))
      (node (ref "U$1") (pin "L1") (pinfunction "REF_ELEC_L1") (pintype "input"))
    )
    (net (code "92") (name "/SD_CS") (class "Default")
      (node (ref "U$3") (pin "P$2") (pinfunction "CS(DAT3)_P$2") (pintype "input"))
      (node (ref "U$6") (pin "P$12") (pinfunction "PA2_P$12") (pintype "bidirectional"))
    )
    (net (code "93") (name "/SD_DET") (class "Default")
      (node (ref "U$3") (pin "G") (pinfunction "CARD_DETECT_G") (pintype "passive"))
      (node (ref "U$6") (pin "P$18") (pinfunction "PB0_P$18") (pintype "bidirectional"))
    )
    (net (code "94") (name "/SD_MISO") (class "Default")
      (node (ref "U$3") (pin "P$7") (pinfunction "DATA_OUT(DAT0)_P$7") (pintype "output"))
      (node (ref "U$6") (pin "P$16") (pinfunction "PA6_P$16") (pintype "bidirectional"))
    )
    (net (code "95") (name "/SD_MOSI") (class "Default")
      (node (ref "U$3") (pin "P$3") (pinfunction "DATA_IN(CMD)_P$3") (pintype "input"))
      (node (ref "U$6") (pin "P$17") (pinfunction "PA7_P$17") (pintype "bidirectional"))
    )
    (net (code "96") (name "/SD_SCK") (class "Default")
      (node (ref "U$3") (pin "P$5") (pinfunction "SCLK_P$5") (pintype "input"))
      (node (ref "U$6") (pin "P$15") (pinfunction "PA5_P$15") (pintype "bidirectional"))
    )
    (net (code "97") (name "/SWCLK") (class "Default")
      (node (ref "U$2") (pin "P$1") (pinfunction "P$1_P$1") (pintype "bidirectional"))
      (node (ref "U$6") (pin "P$37") (pinfunction "PA14_P$37") (pintype "bidirectional"))
    )
    (net (code "98") (name "/SWDIO") (class "Default")
      (node (ref "U$2") (pin "P$2") (pinfunction "P$2_P$2") (pintype "bidirectional"))
      (node (ref "U$6") (pin "P$34") (pinfunction "PA13_P$34") (pintype "bidirectional"))
    )
    (net (code "99") (name "/USB_D+") (class "Default")
      (node (ref "U$12") (pin "P$3") (pinfunction "P$3_P$3") (pintype "bidirectional"))
      (node (ref "U$6") (pin "P$33") (pinfunction "PA12_P$33") (pintype "bidirectional"))
    )
    (net (code "100") (name "/USB_D-") (class "Default")
      (node (ref "U$12") (pin "P$2") (pinfunction "P$2_P$2") (pintype "bidirectional"))
      (node (ref "U$6") (pin "P$32") (pinfunction "PA11_P$32") (pintype "bidirectional"))
    )
    (net (code "101") (name "/V12") (class "Default")
      (node (ref "C26") (pin "2") (pinfunction "2_2") (pintype "passive"))
      (node (ref "U$6") (pin "P$22") (pinfunction "VCAP1_P$22") (pintype "bidirectional"))
    )
    (net (code "102") (name "/VBATT") (class "Default")
      (node (ref "C11") (pin "1") (pinfunction "1_1") (pintype "passive"))
      (node (ref "C19") (pin "2") (pinfunction "2_2") (pintype "passive"))
      (node (ref "C7") (pin "1") (pinfunction "1_1") (pintype "passive"))
      (node (ref "R1") (pin "1") (pinfunction "1_1") (pintype "passive"))
      (node (ref "R12") (pin "2") (pinfunction "2_2") (pintype "passive"))
      (node (ref "SB$1") (pin "1") (pinfunction "1_1") (pintype "passive"))
      (node (ref "U$22") (pin "P$4") (pinfunction "VOUT_P$4") (pintype "bidirectional"))
      (node (ref "U$5") (pin "A2") (pinfunction "EN_A2") (pintype "input"))
      (node (ref "U$5") (pin "B2") (pinfunction "VIN_B2") (pintype "power_in"))
      (node (ref "U$7") (pin "B2") (pinfunction "VIN_B2") (pintype "power_in"))
    )
    (net (code "103") (name "/VBATT_IN") (class "Default")
      (node (ref "C2") (pin "2") (pinfunction "2_2") (pintype "passive"))
      (node (ref "SB$1") (pin "2") (pinfunction "2_2") (pintype "passive"))
      (node (ref "U$11") (pin "P$1") (pinfunction "OUT_P$1") (pintype "passive"))
      (node (ref "U$12") (pin "P$1") (pinfunction "P$1_P$1") (pintype "bidirectional"))
      (node (ref "U$13") (pin "P$2") (pinfunction "P$2_P$2") (pintype "bidirectional"))
      (node (ref "U$22") (pin "P$1") (pinfunction "VIN_P$1") (pintype "bidirectional"))
      (node (ref "U$22") (pin "P$8") (pinfunction "EN_P$8") (pintype "bidirectional"))
      (node (ref "U$6") (pin "P$1") (pinfunction "VBAT_P$1") (pintype "bidirectional"))
    )
    (net (code "104") (name "/VCC") (class "Default")
      (node (ref "C16") (pin "1") (pinfunction "1_1") (pintype "passive"))
      (node (ref "R8") (pin "1") (pinfunction "1_1") (pintype "passive"))
      (node (ref "U$1") (pin "L15") (pinfunction "VDD1_L15") (pintype "power_in"))
      (node (ref "U$1") (pin "M15") (pinfunction "VDD3_M15") (pintype "power_in"))
      (node (ref "U$1") (pin "M2") (pinfunction "VDD2_M2") (pintype "power_in"))
      (node (ref "U$9") (pin "B1") (pinfunction "VOUT_B1") (pintype "power_in"))
    )
    (net (code "105") (name "/VCC_EN") (class "Default")
      (node (ref "U$6") (pin "P$29") (pinfunction "PA8_P$29") (pintype "bidirectional"))
      (node (ref "U$9") (pin "A2") (pinfunction "EN_A2") (pintype "input"))
    )
    (net (code "106") (name "/VDD") (class "Default")
      (node (ref "C1") (pin "2") (pinfunction "2_2") (pintype "passive"))
      (node (ref "C23") (pin "2") (pinfunction "2_2") (pintype "passive"))
      (node (ref "C24") (pin "2") (pinfunction "2_2") (pintype "passive"))
      (node (ref "C25") (pin "2") (pinfunction "2_2") (pintype "passive"))
      (node (ref "C3") (pin "2") (pinfunction "2_2") (pintype "passive"))
      (node (ref "C6") (pin "1") (pinfunction "1_1") (pintype "passive"))
      (node (ref "C9") (pin "2") (pinfunction "2_2") (pintype "passive"))
      (node (ref "R10") (pin "1") (pinfunction "1_1") (pintype "passive"))
      (node (ref "R2") (pin "1") (pinfunction "1_1") (pintype "passive"))
      (node (ref "R5") (pin "1") (pinfunction "1_1") (pintype "passive"))
      (node (ref "U$10") (pin "P$2") (pinfunction "P15_ROLE_P$2") (pintype "bidirectional"))
      (node (ref "U$10") (pin "P$7") (pinfunction "VCC_P$7") (pintype "bidirectional"))
      (node (ref "U$14") (pin "P$8") (pinfunction "VDD_P$8") (pintype "bidirectional"))
      (node (ref "U$20") (pin "P$12") (pinfunction "CSB_P$12") (pintype "bidirectional"))
      (node (ref "U$20") (pin "P$5") (pinfunction "VDDIO_P$5") (pintype "bidirectional"))
      (node (ref "U$20") (pin "P$8") (pinfunction "VDD_P$8") (pintype "bidirectional"))
      (node (ref "U$4") (pin "A1") (pinfunction "VDDA_A1") (pintype "bidirectional"))
      (node (ref "U$5") (pin "B1") (pinfunction "VOUT_B1") (pintype "power_in"))
      (node (ref "U$6") (pin "P$24") (pinfunction "VDD0_P$24") (pintype "bidirectional"))
      (node (ref "U$6") (pin "P$36") (pinfunction "VDD1_P$36") (pintype "bidirectional"))
      (node (ref "U$6") (pin "P$48") (pinfunction "VDD2_P$48") (pintype "bidirectional"))
      (node (ref "U$6") (pin "P$7") (pinfunction "NRST_P$7") (pintype "bidirectional"))
      (node (ref "U$6") (pin "P$9") (pinfunction "VDDA/VREF+_P$9") (pintype "bidirectional"))
      (node (ref "U$8") (pin "P$2") (pinfunction "P$2_P$2") (pintype "bidirectional"))
    )
    (net (code "107") (name "/VEE") (class "Default")
      (node (ref "C14") (pin "2") (pinfunction "2_2") (pintype "passive"))
      (node (ref "C8") (pin "1") (pinfunction "1_1") (pintype "passive"))
      (node (ref "U$3") (pin "P$4") (pinfunction "SD_VDD_P$4") (pintype "power_in"))
      (node (ref "U$7") (pin "B1") (pinfunction "VOUT_B1") (pintype "power_in"))
    )
    (net (code "108") (name "/VEE_EN") (class "Default")
      (node (ref "U$6") (pin "P$25") (pinfunction "PB12_P$25") (pintype "bidirectional"))
      (node (ref "U$7") (pin "A2") (pinfunction "EN_A2") (pintype "input"))
    )
    (net (code "109") (name "/VESD") (class "Default")
      (node (ref "R14") (pin "2") (pinfunction "2_2") (pintype "passive"))
      (node (ref "R8") (pin "2") (pinfunction "2_2") (pintype "passive"))
      (node (ref "U$1") (pin "L2") (pinfunction "VESD_L2") (pintype "power_in"))
    )
    (net (code "110") (name "/VTEST") (class "Default")
      (node (ref "R_TEST") (pin "1") (pinfunction "1_1") (pintype "passive"))
      (node (ref "U$1") (pin "K17") (pinfunction "ELEC_TEST_K17") (pintype "input"))
      (node (ref "U$6") (pin "P$19") (pinfunction "PB1_P$19") (pintype "bidirectional"))
    )
    (net (code "111") (name "GND") (class "Default")
      (node (ref "C10") (pin "2") (pinfunction "2_2") (pintype "passive"))
      (node (ref "C12") (pin "2") (pinfunction "2_2") (pintype "passive"))
      (node (ref "C16") (pin "2") (pinfunction "2_2") (pintype "passive"))
      (node (ref "C4") (pin "2") (pinfunction "2_2") (pintype "passive"))
      (node (ref "C5") (pin "2") (pinfunction "2_2") (pintype "passive"))
      (node (ref "R14") (pin "1") (pinfunction "1_1") (pintype "passive"))
      (node (ref "R4") (pin "2") (pinfunction "2_2") (pintype "passive"))
      (node (ref "R6") (pin "2") (pinfunction "2_2") (pintype "passive"))
      (node (ref "R9") (pin "2") (pinfunction "2_2") (pintype "passive"))
      (node (ref "S1") (pin "B1") (pinfunction "B1_B1") (pintype "passive"))
      (node (ref "S1") (pin "T18") (pinfunction "T18_T18") (pintype "passive"))
      (node (ref "S3") (pin "B1") (pinfunction "B1_B1") (pintype "passive"))
      (node (ref "S3") (pin "T18") (pinfunction "T18_T18") (pintype "passive"))
      (node (ref "U$1") (pin "J1") (pinfunction "NC1_J1") (pintype "power_in"))
      (node (ref "U$1") (pin "J17") (pinfunction "NC2_J17") (pintype "power_in"))
      (node (ref "U$1") (pin "K1") (pinfunction "NC3_K1") (pintype "power_in"))
      (node (ref "U$1") (pin "K16") (pinfunction "NC5_K16") (pintype "power_in"))
      (node (ref "U$1") (pin "K2") (pinfunction "NC4_K2") (pintype "power_in"))
      (node (ref "U$1") (pin "L10") (pinfunction "NC13_L10") (pintype "power_in"))
      (node (ref "U$1") (pin "L11") (pinfunction "NC14_L11") (pintype "power_in"))
      (node (ref "U$1") (pin "L12") (pinfunction "NC15_L12") (pintype "power_in"))
      (node (ref "U$1") (pin "L13") (pinfunction "NC16_L13") (pintype "power_in"))
      (node (ref "U$1") (pin "L14") (pinfunction "NC17_L14") (pintype "power_in"))
      (node (ref "U$1") (pin "L16") (pinfunction "LVDS_EN_L16") (pintype "input"))
      (node (ref "U$1") (pin "L17") (pinfunction "GND1_L17") (pintype "power_in"))
      (node (ref "U$1") (pin "L3") (pinfunction "NC6_L3") (pintype "power_in"))
      (node (ref "U$1") (pin "L4") (pinfunction "NC7_L4") (pintype "power_in"))
      (node (ref "U$1") (pin "L5") (pinfunction "NC8_L5") (pintype "power_in"))
      (node (ref "U$1") (pin "L6") (pinfunction "NC9_L6") (pintype "power_in"))
      (node (ref "U$1") (pin "L7") (pinfunction "NC10_L7") (pintype "power_in"))
      (node (ref "U$1") (pin "L8") (pinfunction "NC11_L8") (pintype "power_in"))
      (node (ref "U$1") (pin "L9") (pinfunction "NC12_L9") (pintype "power_in"))
      (node (ref "U$1") (pin "M1") (pinfunction "GND2_M1") (pintype "power_in"))
      (node (ref "U$1") (pin "M6") (pinfunction "GND3_M6") (pintype "power_in"))
      (node (ref "U$18") (pin "P$2") (pinfunction "P$2_P$2") (pintype "bidirectional"))
      (node (ref "U$9") (pin "A1") (pinfunction "GND_A1") (pintype "power_in"))
    )
    (net (code "112") (name "Net-(U$9-VIN)") (class "Default")
      (node (ref "C10") (pin "1") (pinfunction "1_1") (pintype "passive"))
      (node (ref "C12") (pin "1") (pinfunction "1_1") (pintype "passive"))
      (node (ref "C5") (pin "1") (pinfunction "1_1") (pintype "passive"))
      (node (ref "R1") (pin "2") (pinfunction "2_2") (pintype "passive"))
      (node (ref "U$9") (pin "B2") (pinfunction "VIN_B2") (pintype "power_in"))
    )
    (net (code "113") (name "Net-(U$16-IN)") (class "Default")
      (node (ref "R3") (pin "1") (pinfunction "1_1") (pintype "passive"))
      (node (ref "U$16") (pin "P$2") (pinfunction "IN_P$2") (pintype "passive"))
    )
    (net (code "114") (name "Net-(U$20-ASCX)") (class "Default")
      (node (ref "R10") (pin "2") (pinfunction "2_2") (pintype "passive"))
      (node (ref "R11") (pin "2") (pinfunction "2_2") (pintype "passive"))
      (node (ref "U$20") (pin "P$2") (pinfunction "ASDX_P$2") (pintype "bidirectional"))
      (node (ref "U$20") (pin "P$3") (pinfunction "ASCX_P$3") (pintype "bidirectional"))
    )
    (net (code "115") (name "Net-(U$22-FB)") (class "Default")
      (node (ref "R12") (pin "1") (pinfunction "1_1") (pintype "passive"))
      (node (ref "R13") (pin "2") (pinfunction "2_2") (pintype "passive"))
      (node (ref "U$22") (pin "P$5") (pinfunction "FB_P$5") (pintype "bidirectional"))
    )
    (net (code "116") (name "unconnected-(U$1-AUXOUT-PadM16)") (class "Default")
      (node (ref "U$1") (pin "M16") (pinfunction "AUXOUT_M16") (pintype "tri_state"))
    )
    (net (code "117") (name "unconnected-(U$1-MISO--PadM13)") (class "Default")
      (node (ref "U$1") (pin "M13") (pinfunction "MISO-_M13") (pintype "output"))
    )
    (net (code "118") (name "unconnected-(U$1-MOSI--PadM11)") (class "Default")
      (node (ref "U$1") (pin "M11") (pinfunction "MOSI-_M11") (pintype "input"))
    )
    (net (code "119") (name "unconnected-(U$1-PadCTR)") (class "Default")
      (node (ref "U$1") (pin "CTR") (pinfunction "CTR_CTR") (pintype "bidirectional"))
    )
    (net (code "120") (name "unconnected-(U$1-SCLK--PadM9)") (class "Default")
      (node (ref "U$1") (pin "M9") (pinfunction "SCLK-_M9") (pintype "input"))
    )
    (net (code "121") (name "unconnected-(U$1-~{CS}--PadM7)") (class "Default")
      (node (ref "U$1") (pin "M7") (pinfunction "~{CS}-_M7") (pintype "input"))
    )
    (net (code "122") (name "unconnected-(U$6-PB2{slash}BOOT1-PadP$20)") (class "Default")
      (node (ref "U$6") (pin "P$20") (pinfunction "PB2/BOOT1_P$20") (pintype "bidirectional"))
    )
    (net (code "123") (name "unconnected-(U$10-ANT-PadP$12)") (class "Default")
      (node (ref "U$10") (pin "P$12") (pinfunction "ANT_P$12") (pintype "bidirectional"))
    )
    (net (code "124") (name "unconnected-(U$10-P11_DRDY-PadP$4)") (class "Default")
      (node (ref "U$10") (pin "P$4") (pinfunction "P11_DRDY_P$4") (pintype "bidirectional"))
    )
    (net (code "125") (name "unconnected-(U$10-P13_STATE-PadP$1)") (class "Default")
      (node (ref "U$10") (pin "P$1") (pinfunction "P13_STATE_P$1") (pintype "bidirectional"))
    )
    (net (code "126") (name "unconnected-(U$10-VPP-PadP$11)") (class "Default")
      (node (ref "U$10") (pin "P$11") (pinfunction "VPP_P$11") (pintype "bidirectional"))
    )
    (net (code "127") (name "unconnected-(U$20-INT1-PadP$4)") (class "Default")
      (node (ref "U$20") (pin "P$4") (pinfunction "INT1_P$4") (pintype "bidirectional"))
    )
    (net (code "128") (name "unconnected-(U$20-INT2-PadP$9)") (class "Default")
      (node (ref "U$20") (pin "P$9") (pinfunction "INT2_P$9") (pintype "bidirectional"))
    )
    (net (code "129") (name "unconnected-(U$20-OSCB-PadP$10)") (class "Default")
      (node (ref "U$20") (pin "P$10") (pinfunction "OSCB_P$10") (pintype "bidirectional"))
    )
    (net (code "130") (name "unconnected-(U$20-OSDO-PadP$11)") (class "Default")
      (node (ref "U$20") (pin "P$11") (pinfunction "OSDO_P$11") (pintype "bidirectional"))
    )
  )
)
